# SCHEMATIC.net
KiCad netlist of a schematic drawn in Altium Designer
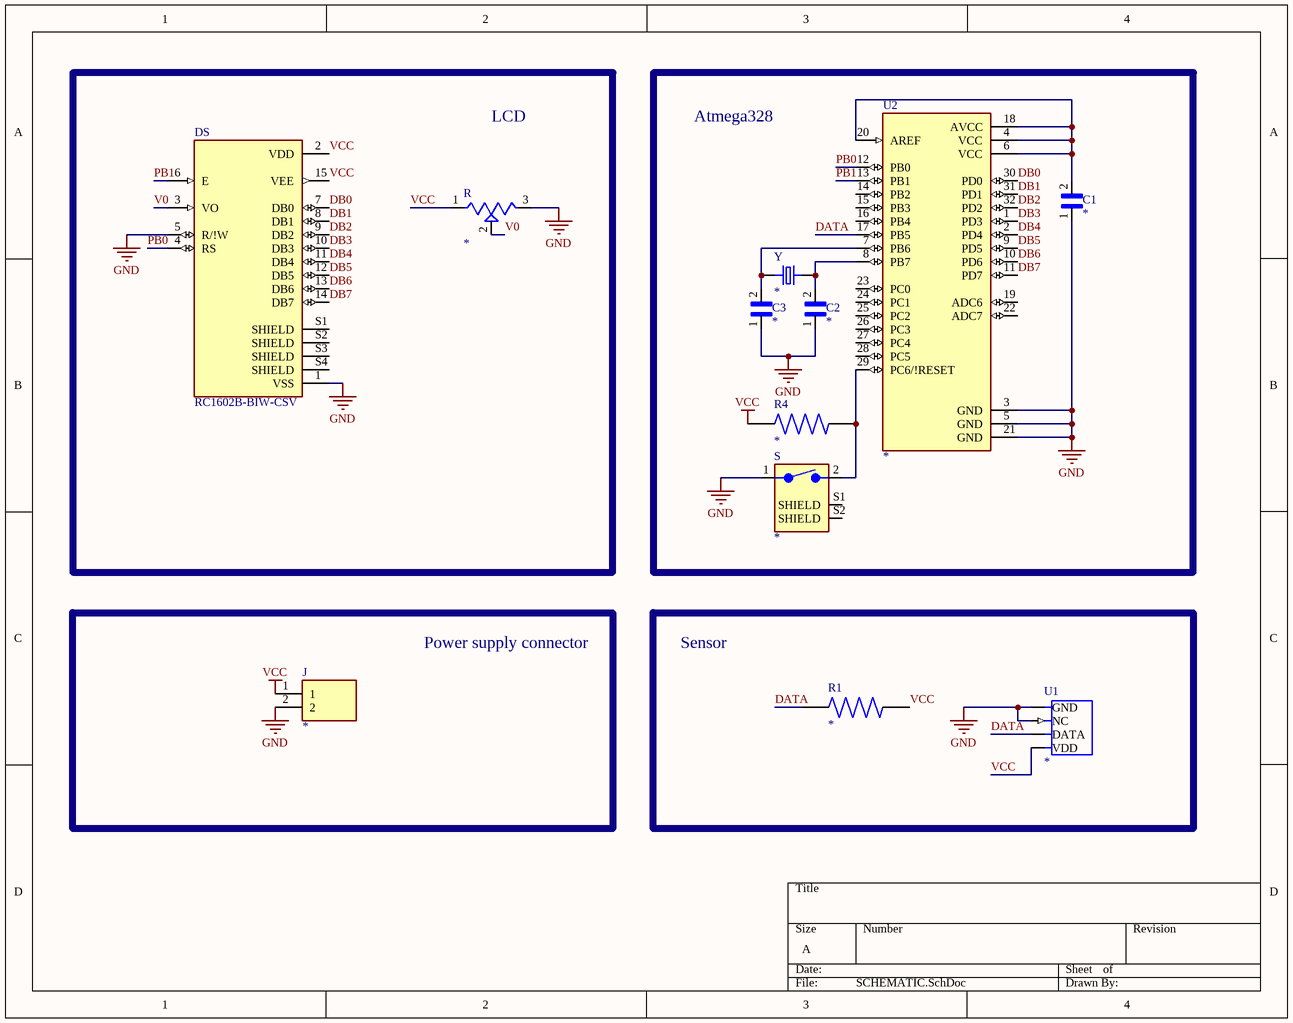
[diagram p0: SCHEMATIC.SchDoc]

(export (version "E")
  (design (tool "Eeschema 10.0.6"))
  (components
    (comp (ref "C1")
      (value "*")
      (footprint "CAPC1414X145N")
      (description "CAP CER 20PF 150V 0505")
      (fields (field (name "MF") "AVX") (field (name "MP") "SQCAEM200JATWE"))
      (libsource (lib "SQCAEM200JATWE") (part "SQCAEM200JATWE"))
    )
    (comp (ref "C2")
      (value "*")
      (footprint "CAPC1414X145N")
      (description "CAP CER 20PF 150V 0505")
      (fields (field (name "MF") "AVX") (field (name "MP") "SQCAEM200JATWE"))
      (libsource (lib "SQCAEM200JATWE") (part "SQCAEM200JATWE"))
    )
    (comp (ref "C3")
      (value "*")
      (footprint "CAPC1414X145N")
      (description "CAP CER 20PF 150V 0505")
      (fields (field (name "MF") "AVX") (field (name "MP") "SQCAEM200JATWE"))
      (libsource (lib "SQCAEM200JATWE") (part "SQCAEM200JATWE"))
    )
    (comp (ref "DS")
      (value "RC1602B-BIW-CSV")
      (footprint "SnapEDApcb:LCD_RC1602B-BIW-CSV")
      (description "Display: LCD; alphanumeric; STN Negative; 16x2; blue; LED; PIN: 16")
      (fields (field (name "MF") "Raystar"))
      (libsource (lib "RC1602B-BIW-CSV") (part "RC1602B-BIW-CSV"))
    )
    (comp (ref "J")
      (value "*")
      (footprint "MOLEX_0039296028")
      (description "Connector Header Through Hole 2 position")
      (fields (field (name "MF") "Molex") (field (name "MP") "0039296028"))
      (libsource (lib "connector") (part "0039296028"))
    )
    (comp (ref "R")
      (value "*")
      (footprint "TRIM_3296W-1-20K")
      (description "Res Trimmer 20K Ohm 10% 1/2W 25Turn 2.19mm Pin Thru-Hole Tube")
      (fields (field (name "MF") "Bourns") (field (name "MP") "3296W-1-20K"))
      (libsource (lib "pot") (part "3296W-1-20K"))
    )
    (comp (ref "R1")
      (value "*")
      (footprint "RESC1608X55N")
      (description "RES 0.027 OHM 5% 1/8W 0603")
      (fields (field (name "MP") "CSR0603JT27L0") (field (name "MF") "Stackpole Electronics Inc"))
      (libsource (lib "CSR0603JT27L0") (part "CSR0603JT27L0"))
    )
    (comp (ref "R4")
      (value "*")
      (footprint "RESC1608X55N")
      (description "RES 0.027 OHM 5% 1/8W 0603")
      (fields (field (name "MP") "CSR0603JT27L0") (field (name "MF") "Stackpole Electronics Inc"))
      (libsource (lib "CSR0603JT27L0") (part "CSR0603JT27L0"))
    )
    (comp (ref "S")
      (value "1-1825027-1")
      (footprint "SW_1-1825027-1")
      (description "Switch Push Button OFF _ON_ SPST Round Button 0.05A 24VDC Momentary Contact PC Pins Thru-Hole")
      (fields (field (name "MF") "TE Connectivity") (field (name "COMMENT_1") "*"))
      (libsource (lib "1-1825027-1") (part "1-1825027-1"))
    )
    (comp (ref "U1")
      (value "*")
      (footprint "SNR4-2.54-25.0X15.0X7.0MM")
      (description "AM2302/DHT22 Humidity, Temperature Sensor mikroBUSâ„¢ Clickâ„¢ Platform Evaluation Expansion Board")
      (fields (field (name "MF") "Seeed Technology") (field (name "MP") "AM2302"))
      (libsource (lib "TEM-HUM-AM2302_4P-25.0X15.0MM_") (part "TEM-HUM-AM2302(4P-25.0X15.0MM)"))
    )
    (comp (ref "U2")
      (value "*")
      (footprint "QFP80P900X900X120-32N")
      (description "AVR AVRÂ® ATmega Microcontroller IC 8-Bit 20MHz 32KB _16K x 16_ FLASH 32-TQFP _7x7_")
      (fields (field (name "MP") "ATMEGA328-AU") (field (name "MF") "Microchip"))
      (libsource (lib "ATMEGA328-AU") (part "ATMEGA328-AU"))
    )
    (comp (ref "Y")
      (value "*")
      (footprint "XTAL_ECS-180-S-5P-DN-TR")
      (description "Crystals 18MHz")
      (fields (field (name "MP") "ECS-180-S-5P-DN-TR") (field (name "MF") "ECS International"))
      (libsource (lib "ECS-180-S-5P-DN-TR") (part "ECS-180-S-5P-DN-TR"))
    )
  )
  (nets
    (net (code "1") (name "/DATA") (class "Default")
      (node (ref "R1") (pin "1") (pinfunction "1_1") (pintype "passive"))
      (node (ref "U1") (pin "P$2") (pinfunction "DATA_P$2") (pintype "bidirectional"))
      (node (ref "U2") (pin "17") (pinfunction "PB5_17") (pintype "bidirectional"))
    )
    (net (code "2") (name "/DB0") (class "Default")
      (node (ref "DS") (pin "7") (pinfunction "DB0_7") (pintype "bidirectional"))
      (node (ref "U2") (pin "30") (pinfunction "PD0_30") (pintype "bidirectional"))
    )
    (net (code "3") (name "/DB1") (class "Default")
      (node (ref "DS") (pin "8") (pinfunction "DB1_8") (pintype "bidirectional"))
      (node (ref "U2") (pin "31") (pinfunction "PD1_31") (pintype "bidirectional"))
    )
    (net (code "4") (name "/DB2") (class "Default")
      (node (ref "DS") (pin "9") (pinfunction "DB2_9") (pintype "bidirectional"))
      (node (ref "U2") (pin "32") (pinfunction "PD2_32") (pintype "bidirectional"))
    )
    (net (code "5") (name "/DB3") (class "Default")
      (node (ref "DS") (pin "10") (pinfunction "DB3_10") (pintype "bidirectional"))
      (node (ref "U2") (pin "1") (pinfunction "PD3_1") (pintype "bidirectional"))
    )
    (net (code "6") (name "/DB4") (class "Default")
      (node (ref "DS") (pin "11") (pinfunction "DB4_11") (pintype "bidirectional"))
      (node (ref "U2") (pin "2") (pinfunction "PD4_2") (pintype "bidirectional"))
    )
    (net (code "7") (name "/DB5") (class "Default")
      (node (ref "DS") (pin "12") (pinfunction "DB5_12") (pintype "bidirectional"))
      (node (ref "U2") (pin "9") (pinfunction "PD5_9") (pintype "bidirectional"))
    )
    (net (code "8") (name "/DB6") (class "Default")
      (node (ref "DS") (pin "13") (pinfunction "DB6_13") (pintype "bidirectional"))
      (node (ref "U2") (pin "10") (pinfunction "PD6_10") (pintype "bidirectional"))
    )
    (net (code "9") (name "/DB7") (class "Default")
      (node (ref "DS") (pin "14") (pinfunction "DB7_14") (pintype "bidirectional"))
      (node (ref "U2") (pin "11") (pinfunction "PD7_11") (pintype "bidirectional"))
    )
    (net (code "10") (name "/PB0") (class "Default")
      (node (ref "DS") (pin "4") (pinfunction "RS_4") (pintype "bidirectional"))
      (node (ref "U2") (pin "12") (pinfunction "PB0_12") (pintype "bidirectional"))
    )
    (net (code "11") (name "/PB1") (class "Default")
      (node (ref "DS") (pin "6") (pinfunction "E_6") (pintype "input"))
      (node (ref "U2") (pin "13") (pinfunction "PB1_13") (pintype "bidirectional"))
    )
    (net (code "12") (name "/V0") (class "Default")
      (node (ref "DS") (pin "3") (pinfunction "VO_3") (pintype "input"))
      (node (ref "R") (pin "2") (pinfunction "WIPER_2") (pintype "passive"))
    )
    (net (code "13") (name "GND") (class "Default")
      (node (ref "C1") (pin "1") (pinfunction "1_1") (pintype "passive"))
      (node (ref "C2") (pin "1") (pinfunction "1_1") (pintype "passive"))
      (node (ref "C3") (pin "1") (pinfunction "1_1") (pintype "passive"))
      (node (ref "DS") (pin "1") (pinfunction "VSS_1") (pintype "power_in"))
      (node (ref "DS") (pin "5") (pinfunction "R/!W_5") (pintype "bidirectional"))
      (node (ref "J") (pin "2") (pinfunction "2_2") (pintype "passive"))
      (node (ref "R") (pin "3") (pinfunction "CW_3") (pintype "passive"))
      (node (ref "S") (pin "1") (pinfunction "1_1") (pintype "passive"))
      (node (ref "U1") (pin "P$3") (pinfunction "NC_P$3") (pintype "input"))
      (node (ref "U1") (pin "P$4") (pinfunction "GND_P$4") (pintype "power_in"))
      (node (ref "U2") (pin "21") (pinfunction "GND_21") (pintype "power_in"))
      (node (ref "U2") (pin "3") (pinfunction "GND_3") (pintype "power_in"))
      (node (ref "U2") (pin "5") (pinfunction "GND_5") (pintype "power_in"))
    )
    (net (code "14") (name "Net-(U2-AREF)") (class "Default")
      (node (ref "C1") (pin "2") (pinfunction "2_2") (pintype "passive"))
      (node (ref "U2") (pin "18") (pinfunction "AVCC_18") (pintype "power_in"))
      (node (ref "U2") (pin "20") (pinfunction "AREF_20") (pintype "input"))
      (node (ref "U2") (pin "4") (pinfunction "VCC_4") (pintype "power_in"))
      (node (ref "U2") (pin "6") (pinfunction "VCC_6") (pintype "power_in"))
    )
    (net (code "15") (name "Net-(U2-PB6)") (class "Default")
      (node (ref "C3") (pin "2") (pinfunction "2_2") (pintype "passive"))
      (node (ref "U2") (pin "7") (pinfunction "PB6_7") (pintype "bidirectional"))
      (node (ref "Y") (pin "1") (pinfunction "1_1") (pintype "passive"))
    )
    (net (code "16") (name "Net-(U2-PB7)") (class "Default")
      (node (ref "C2") (pin "2") (pinfunction "2_2") (pintype "passive"))
      (node (ref "U2") (pin "8") (pinfunction "PB7_8") (pintype "bidirectional"))
      (node (ref "Y") (pin "2") (pinfunction "2_2") (pintype "passive"))
    )
    (net (code "17") (name "Net-(U2-PC6{slash}!RESET)") (class "Default")
      (node (ref "R4") (pin "2") (pinfunction "2_2") (pintype "passive"))
      (node (ref "S") (pin "2") (pinfunction "2_2") (pintype "passive"))
      (node (ref "U2") (pin "29") (pinfunction "PC6/!RESET_29") (pintype "bidirectional"))
    )
    (net (code "18") (name "VCC") (class "Default")
      (node (ref "DS") (pin "15") (pinfunction "VEE_15") (pintype "output"))
      (node (ref "DS") (pin "2") (pinfunction "VDD_2") (pintype "power_in"))
      (node (ref "J") (pin "1") (pinfunction "1_1") (pintype "passive"))
      (node (ref "R") (pin "1") (pinfunction "CCW_1") (pintype "passive"))
      (node (ref "R1") (pin "2") (pinfunction "2_2") (pintype "passive"))
      (node (ref "R4") (pin "1") (pinfunction "1_1") (pintype "passive"))
      (node (ref "U1") (pin "P$1") (pinfunction "VDD_P$1") (pintype "power_in"))
    )
    (net (code "19") (name "unconnected-(DS-SHIELD-PadS1)") (class "Default")
      (node (ref "DS") (pin "S1") (pinfunction "SHIELD_S1") (pintype "passive"))
    )
    (net (code "20") (name "unconnected-(DS-SHIELD-PadS2)") (class "Default")
      (node (ref "DS") (pin "S2") (pinfunction "SHIELD_S2") (pintype "passive"))
    )
    (net (code "21") (name "unconnected-(DS-SHIELD-PadS3)") (class "Default")
      (node (ref "DS") (pin "S3") (pinfunction "SHIELD_S3") (pintype "passive"))
    )
    (net (code "22") (name "unconnected-(DS-SHIELD-PadS4)") (class "Default")
      (node (ref "DS") (pin "S4") (pinfunction "SHIELD_S4") (pintype "passive"))
    )
    (net (code "23") (name "unconnected-(S-SHIELD-PadS1)") (class "Default")
      (node (ref "S") (pin "S1") (pinfunction "SHIELD_S1") (pintype "power_in"))
    )
    (net (code "24") (name "unconnected-(S-SHIELD-PadS2)") (class "Default")
      (node (ref "S") (pin "S2") (pinfunction "SHIELD_S2") (pintype "power_in"))
    )
    (net (code "25") (name "unconnected-(U2-ADC6-Pad19)") (class "Default")
      (node (ref "U2") (pin "19") (pinfunction "ADC6_19") (pintype "bidirectional"))
    )
    (net (code "26") (name "unconnected-(U2-ADC7-Pad22)") (class "Default")
      (node (ref "U2") (pin "22") (pinfunction "ADC7_22") (pintype "bidirectional"))
    )
    (net (code "27") (name "unconnected-(U2-PB2-Pad14)") (class "Default")
      (node (ref "U2") (pin "14") (pinfunction "PB2_14") (pintype "bidirectional"))
    )
    (net (code "28") (name "unconnected-(U2-PB3-Pad15)") (class "Default")
      (node (ref "U2") (pin "15") (pinfunction "PB3_15") (pintype "bidirectional"))
    )
    (net (code "29") (name "unconnected-(U2-PB4-Pad16)") (class "Default")
      (node (ref "U2") (pin "16") (pinfunction "PB4_16") (pintype "bidirectional"))
    )
    (net (code "30") (name "unconnected-(U2-PC0-Pad23)") (class "Default")
      (node (ref "U2") (pin "23") (pinfunction "PC0_23") (pintype "bidirectional"))
    )
    (net (code "31") (name "unconnected-(U2-PC1-Pad24)") (class "Default")
      (node (ref "U2") (pin "24") (pinfunction "PC1_24") (pintype "bidirectional"))
    )
    (net (code "32") (name "unconnected-(U2-PC2-Pad25)") (class "Default")
      (node (ref "U2") (pin "25") (pinfunction "PC2_25") (pintype "bidirectional"))
    )
    (net (code "33") (name "unconnected-(U2-PC3-Pad26)") (class "Default")
      (node (ref "U2") (pin "26") (pinfunction "PC3_26") (pintype "bidirectional"))
    )
    (net (code "34") (name "unconnected-(U2-PC4-Pad27)") (class "Default")
      (node (ref "U2") (pin "27") (pinfunction "PC4_27") (pintype "bidirectional"))
    )
    (net (code "35") (name "unconnected-(U2-PC5-Pad28)") (class "Default")
      (node (ref "U2") (pin "28") (pinfunction "PC5_28") (pintype "bidirectional"))
    )
  )
)
